# schematic_advanced_easyeda_export.net
KiCad netlist of a schematic drawn in EasyEDA
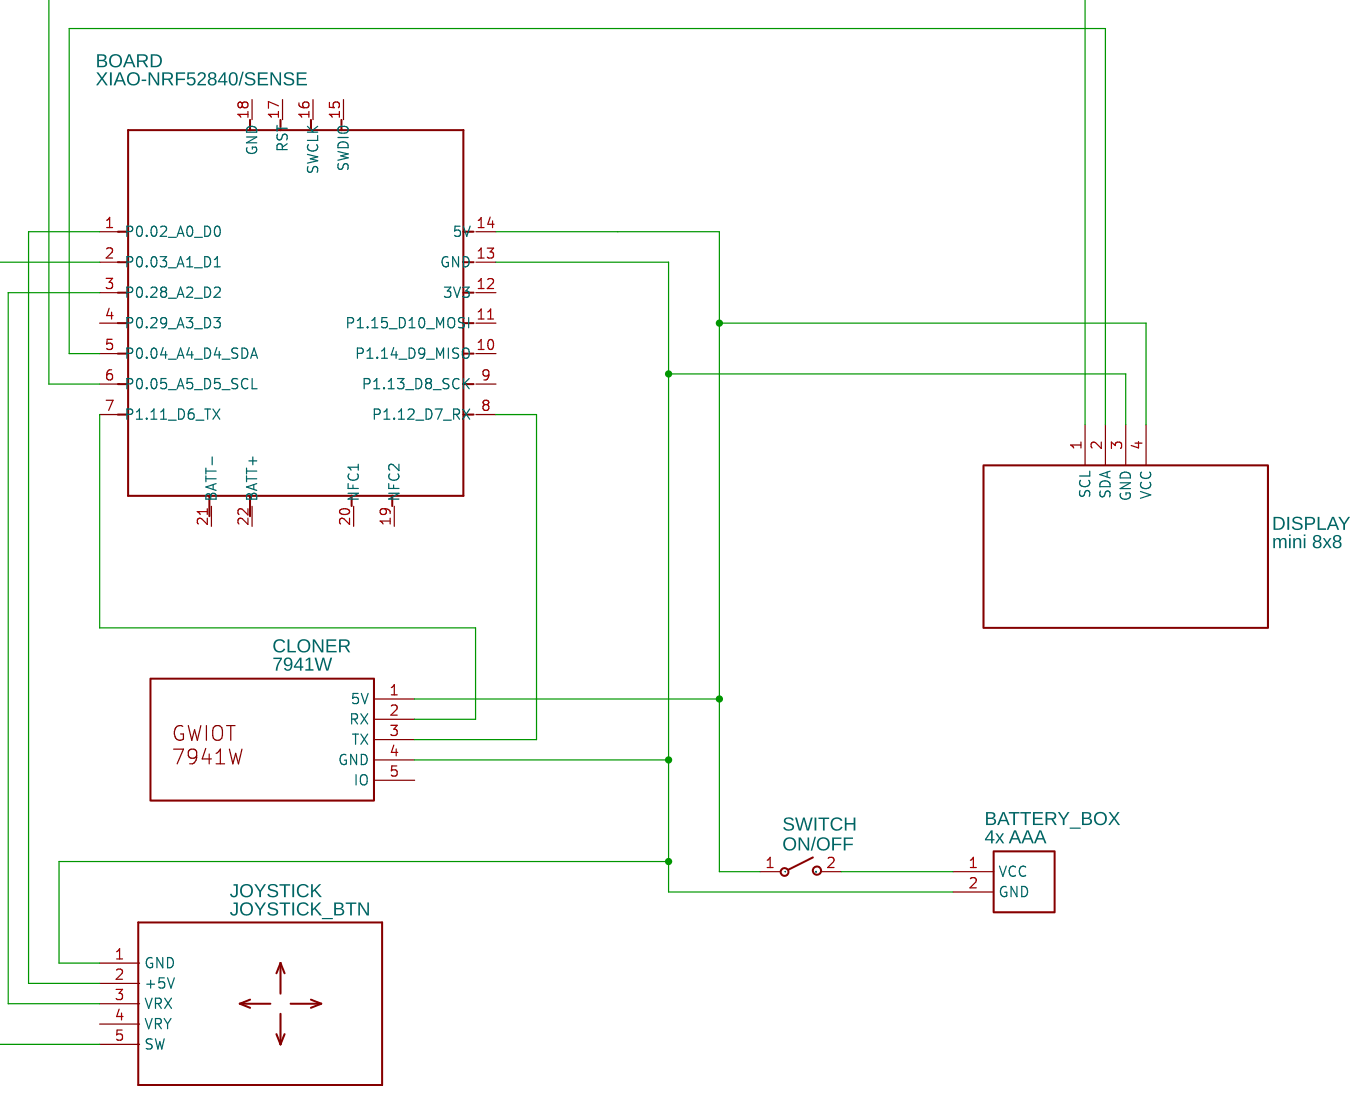
[diagram p0: schematic sheet]

(export (version "E")
  (design (tool "Eeschema 10.0.6"))
  (components
    (comp (ref "BATTERY_BOX")
      (value "4x AAA")
      (fields (field (name "Manufacturer Part") "五号2节并列电池盒") (field (name "Manufacturer") "国产"))
      (libsource (lib "") (part "No.52Section side by side battery box"))
    )
    (comp (ref "BOARD") (value "XIAO-NRF52840/SENSE") (libsource (lib "") (part "XIAO-NRF52840/SENSE")))
    (comp (ref "CLONER")
      (value "7941W")
      (fields (field (name "Manufacturer") "GWIOT"))
      (libsource (lib "") (part "7941W"))
    )
    (comp (ref "DISPLAY") (value "mini 8x8") (libsource (lib "") (part "mini 8x8")))
    (comp (ref "JOYSTICK") (value "JOYSTICK_BTN") (libsource (lib "") (part "JOYSTICK_BTN")))
    (comp (ref "SWITCH") (value "ON/OFF") (libsource (lib "") (part "SW_SPST")))
  )
  (nets
    (net (code "1") (name "Net-(BATTERY_BOX-GND)") (class "Default")
      (node (ref "BATTERY_BOX") (pin "2") (pinfunction "GND_2") (pintype "unspecified"))
      (node (ref "BOARD") (pin "13") (pinfunction "GND_13") (pintype "unspecified"))
      (node (ref "CLONER") (pin "4") (pinfunction "GND_4") (pintype "unspecified"))
      (node (ref "DISPLAY") (pin "3") (pinfunction "GND_3") (pintype "unspecified"))
      (node (ref "JOYSTICK") (pin "1") (pinfunction "GND_1") (pintype "bidirectional"))
    )
    (net (code "2") (name "Net-(BATTERY_BOX-VCC)") (class "Default")
      (node (ref "BATTERY_BOX") (pin "1") (pinfunction "VCC_1") (pintype "unspecified"))
      (node (ref "SWITCH") (pin "2") (pinfunction "B_2") (pintype "input"))
    )
    (net (code "3") (name "Net-(BOARD-5V)") (class "Default")
      (node (ref "BOARD") (pin "14") (pinfunction "5V_14") (pintype "unspecified"))
      (node (ref "CLONER") (pin "1") (pinfunction "5V_1") (pintype "unspecified"))
      (node (ref "DISPLAY") (pin "4") (pinfunction "VCC_4") (pintype "unspecified"))
      (node (ref "SWITCH") (pin "1") (pinfunction "A_1") (pintype "input"))
    )
    (net (code "4") (name "Net-(BOARD-P0.02_A0_D0)") (class "Default")
      (node (ref "BOARD") (pin "1") (pinfunction "P0.02_A0_D0_1") (pintype "unspecified"))
      (node (ref "JOYSTICK") (pin "2") (pinfunction "+5V_2") (pintype "bidirectional"))
    )
    (net (code "5") (name "Net-(BOARD-P0.03_A1_D1)") (class "Default")
      (node (ref "BOARD") (pin "2") (pinfunction "P0.03_A1_D1_2") (pintype "unspecified"))
      (node (ref "JOYSTICK") (pin "5") (pinfunction "SW_5") (pintype "bidirectional"))
    )
    (net (code "6") (name "Net-(BOARD-P0.04_A4_D4_SDA)") (class "Default")
      (node (ref "BOARD") (pin "5") (pinfunction "P0.04_A4_D4_SDA_5") (pintype "unspecified"))
      (node (ref "DISPLAY") (pin "2") (pinfunction "SDA_2") (pintype "unspecified"))
    )
    (net (code "7") (name "Net-(BOARD-P0.05_A5_D5_SCL)") (class "Default")
      (node (ref "BOARD") (pin "6") (pinfunction "P0.05_A5_D5_SCL_6") (pintype "unspecified"))
      (node (ref "DISPLAY") (pin "1") (pinfunction "SCL_1") (pintype "unspecified"))
    )
    (net (code "8") (name "Net-(BOARD-P0.28_A2_D2)") (class "Default")
      (node (ref "BOARD") (pin "3") (pinfunction "P0.28_A2_D2_3") (pintype "unspecified"))
      (node (ref "JOYSTICK") (pin "3") (pinfunction "VRX_3") (pintype "bidirectional"))
    )
    (net (code "9") (name "Net-(BOARD-P1.11_D6_TX)") (class "Default")
      (node (ref "BOARD") (pin "7") (pinfunction "P1.11_D6_TX_7") (pintype "unspecified"))
      (node (ref "CLONER") (pin "2") (pinfunction "RX_2") (pintype "unspecified"))
    )
    (net (code "10") (name "Net-(BOARD-P1.12_D7_RX)") (class "Default")
      (node (ref "BOARD") (pin "8") (pinfunction "P1.12_D7_RX_8") (pintype "unspecified"))
      (node (ref "CLONER") (pin "3") (pinfunction "TX_3") (pintype "unspecified"))
    )
    (net (code "11") (name "unconnected-(BOARD-3V3-Pad12)") (class "Default")
      (node (ref "BOARD") (pin "12") (pinfunction "3V3_12") (pintype "unspecified"))
    )
    (net (code "12") (name "unconnected-(BOARD-BATT+-Pad22)") (class "Default")
      (node (ref "BOARD") (pin "22") (pinfunction "BATT+_22") (pintype "unspecified"))
    )
    (net (code "13") (name "unconnected-(BOARD-BATT--Pad21)") (class "Default")
      (node (ref "BOARD") (pin "21") (pinfunction "BATT-_21") (pintype "unspecified"))
    )
    (net (code "14") (name "unconnected-(BOARD-GND-Pad18)") (class "Default")
      (node (ref "BOARD") (pin "18") (pinfunction "GND_18") (pintype "unspecified"))
    )
    (net (code "15") (name "unconnected-(BOARD-NFC1-Pad20)") (class "Default")
      (node (ref "BOARD") (pin "20") (pinfunction "NFC1_20") (pintype "unspecified"))
    )
    (net (code "16") (name "unconnected-(BOARD-NFC2-Pad19)") (class "Default")
      (node (ref "BOARD") (pin "19") (pinfunction "NFC2_19") (pintype "unspecified"))
    )
    (net (code "17") (name "unconnected-(BOARD-P0.29_A3_D3-Pad4)") (class "Default")
      (node (ref "BOARD") (pin "4") (pinfunction "P0.29_A3_D3_4") (pintype "unspecified"))
    )
    (net (code "18") (name "unconnected-(BOARD-P1.13_D8_SCK-Pad9)") (class "Default")
      (node (ref "BOARD") (pin "9") (pinfunction "P1.13_D8_SCK_9") (pintype "unspecified"))
    )
    (net (code "19") (name "unconnected-(BOARD-P1.14_D9_MISO-Pad10)") (class "Default")
      (node (ref "BOARD") (pin "10") (pinfunction "P1.14_D9_MISO_10") (pintype "unspecified"))
    )
    (net (code "20") (name "unconnected-(BOARD-P1.15_D10_MOSI-Pad11)") (class "Default")
      (node (ref "BOARD") (pin "11") (pinfunction "P1.15_D10_MOSI_11") (pintype "unspecified"))
    )
    (net (code "21") (name "unconnected-(BOARD-RST-Pad17)") (class "Default")
      (node (ref "BOARD") (pin "17") (pinfunction "RST_17") (pintype "unspecified"))
    )
    (net (code "22") (name "unconnected-(BOARD-SWCLK-Pad16)") (class "Default")
      (node (ref "BOARD") (pin "16") (pinfunction "SWCLK_16") (pintype "unspecified"))
    )
    (net (code "23") (name "unconnected-(BOARD-SWDIO-Pad15)") (class "Default")
      (node (ref "BOARD") (pin "15") (pinfunction "SWDIO_15") (pintype "unspecified"))
    )
    (net (code "24") (name "unconnected-(CLONER-IO-Pad5)") (class "Default")
      (node (ref "CLONER") (pin "5") (pinfunction "IO_5") (pintype "unspecified"))
    )
    (net (code "25") (name "unconnected-(JOYSTICK-VRY-Pad4)") (class "Default")
      (node (ref "JOYSTICK") (pin "4") (pinfunction "VRY_4") (pintype "bidirectional"))
    )
  )
)
